# 47_VI-Camera_MIPI-CSI.net
KiCad netlist of a schematic drawn in Altium Designer
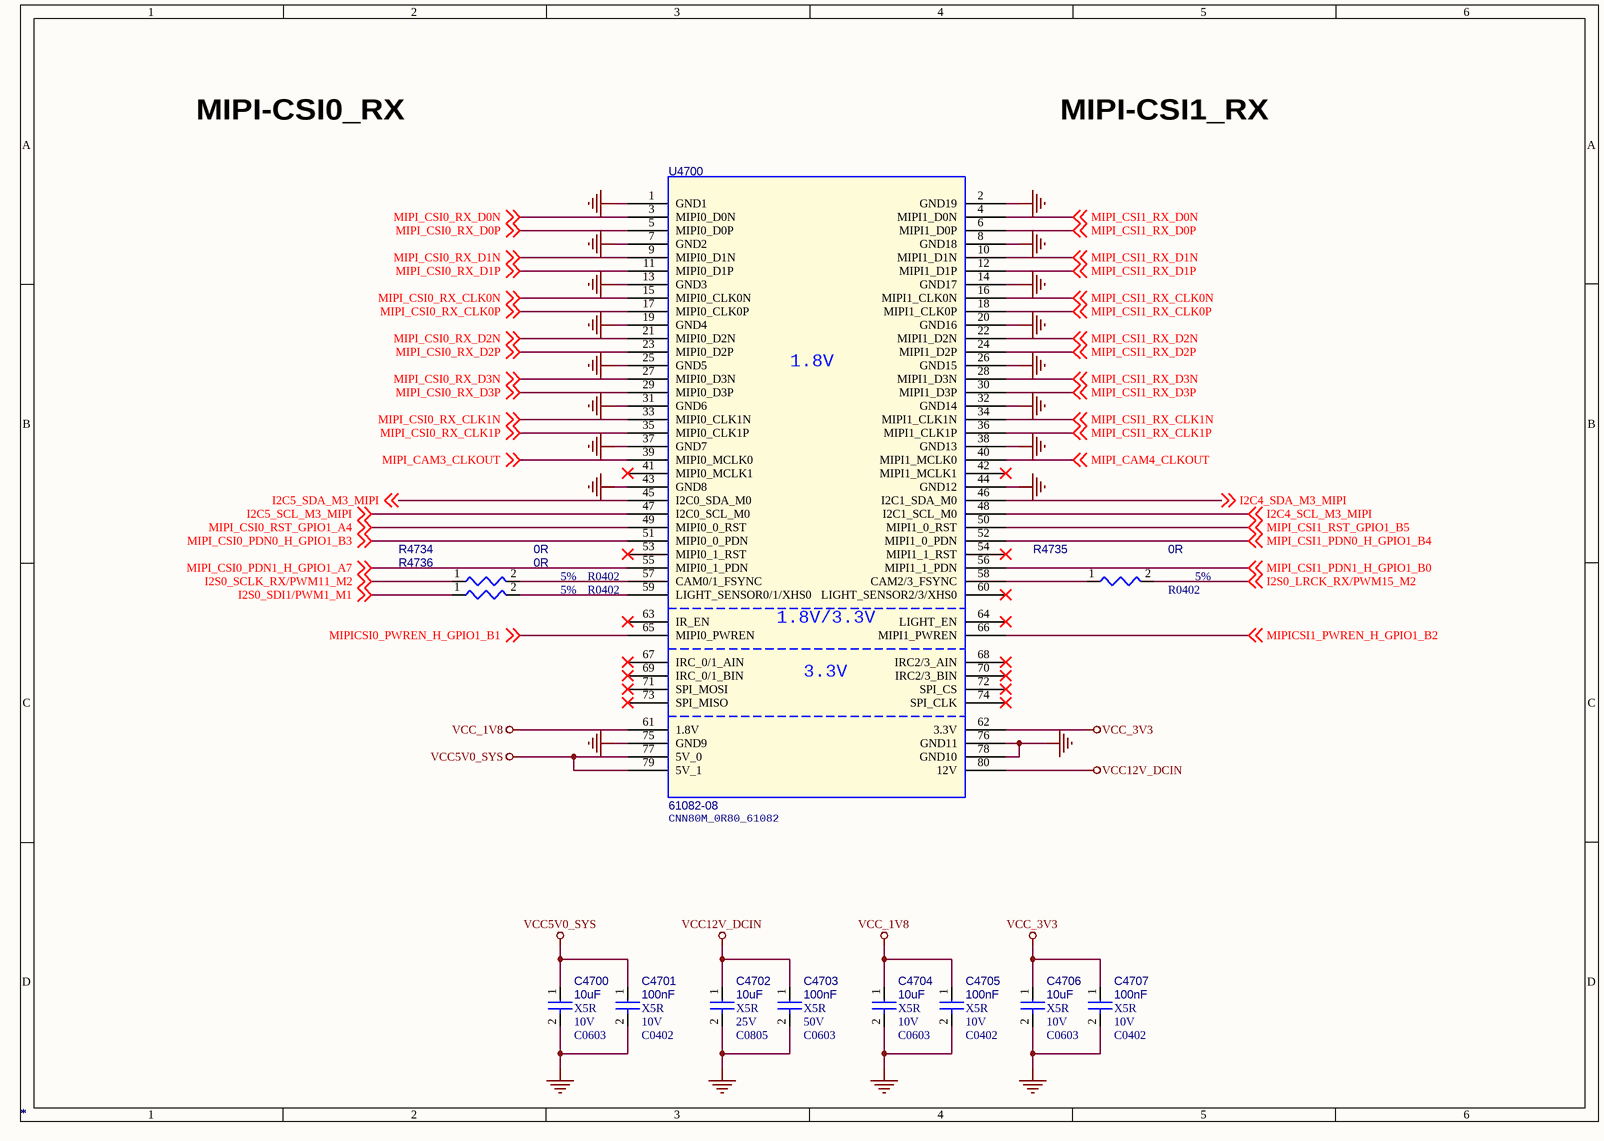
[diagram p0: 47.VI-Camera_MIPI-CSI.SchDoc]

(export (version "E")
  (design (tool "Eeschema 10.0.6"))
  (components
    (comp (ref "C4700")
      (value "*")
      (footprint "C0603")
      (description "cap,10.00uF,+/-10%,10V,X5R,C0603")
      (fields
        (field (name "VOLTAGE") "10V")
        (field (name "PCB FOOTPRINT") "C0603")
        (field (name "DIELECTRIC") "X5R")
        (field (name "TOLERANCE") "10%")
        (field (name "MANUFACTURER") "TDK")
        (field (name "ALTIUM_UNNAMED_1") "10uF")
        (field (name "CREATED BY") "JJJ")
      )
      (libsource (lib "*") (part "CAP NP"))
    )
    (comp (ref "C4701")
      (value "*")
      (footprint "C0402")
      (description "cap,100.00nF,+/-10%,10V,X5R,C0402")
      (fields
        (field (name "VOLTAGE") "10V")
        (field (name "PCB FOOTPRINT") "C0402")
        (field (name "DIELECTRIC") "X5R")
        (field (name "MANUFACTURER") "TDK")
        (field (name "TOLERANCE") "10%")
        (field (name "ALTIUM_UNNAMED_1") "100nF")
        (field (name "CREATED BY") "JJJ")
      )
      (libsource (lib "*") (part "CAP NP"))
    )
    (comp (ref "C4702")
      (value "*")
      (footprint "C0805")
      (description "cap,10.00uF,+/-10%,25V,X5R,C0805")
      (fields
        (field (name "VOLTAGE") "25V")
        (field (name "PCB FOOTPRINT") "C0805")
        (field (name "DIELECTRIC") "X5R")
        (field (name "TOLERANCE") "10%")
        (field (name "MANUFACTURER") "TDK")
        (field (name "ALTIUM_UNNAMED_1") "10uF")
        (field (name "CREATED BY") "JJJ")
      )
      (libsource (lib "*") (part "CAP NP"))
    )
    (comp (ref "C4703")
      (value "*")
      (footprint "C0603")
      (description "cap,100.00nF,+/-10%,50V,X5R,C0603")
      (fields
        (field (name "VOLTAGE") "50V")
        (field (name "PCB FOOTPRINT") "C0603")
        (field (name "DIELECTRIC") "X5R")
        (field (name "MANUFACTURER") "TDK")
        (field (name "TOLERANCE") "10%")
        (field (name "ALTIUM_UNNAMED_1") "100nF")
        (field (name "CREATED BY") "JJJ")
      )
      (libsource (lib "*") (part "CAP NP"))
    )
    (comp (ref "C4704")
      (value "*")
      (footprint "C0603")
      (description "cap,10.00uF,+/-10%,10V,X5R,C0603")
      (fields
        (field (name "VOLTAGE") "10V")
        (field (name "PCB FOOTPRINT") "C0603")
        (field (name "DIELECTRIC") "X5R")
        (field (name "TOLERANCE") "10%")
        (field (name "MANUFACTURER") "TDK")
        (field (name "ALTIUM_UNNAMED_1") "10uF")
        (field (name "CREATED BY") "JJJ")
      )
      (libsource (lib "*") (part "CAP NP"))
    )
    (comp (ref "C4705")
      (value "*")
      (footprint "C0402")
      (description "cap,100.00nF,+/-10%,10V,X5R,C0402")
      (fields
        (field (name "VOLTAGE") "10V")
        (field (name "PCB FOOTPRINT") "C0402")
        (field (name "DIELECTRIC") "X5R")
        (field (name "MANUFACTURER") "TDK")
        (field (name "TOLERANCE") "10%")
        (field (name "ALTIUM_UNNAMED_1") "100nF")
        (field (name "CREATED BY") "JJJ")
      )
      (libsource (lib "*") (part "CAP NP"))
    )
    (comp (ref "C4706")
      (value "*")
      (footprint "C0603")
      (description "cap,10.00uF,+/-10%,10V,X5R,C0603")
      (fields
        (field (name "VOLTAGE") "10V")
        (field (name "PCB FOOTPRINT") "C0603")
        (field (name "DIELECTRIC") "X5R")
        (field (name "TOLERANCE") "10%")
        (field (name "MANUFACTURER") "TDK")
        (field (name "ALTIUM_UNNAMED_1") "10uF")
        (field (name "CREATED BY") "JJJ")
      )
      (libsource (lib "*") (part "CAP NP"))
    )
    (comp (ref "C4707")
      (value "*")
      (footprint "C0402")
      (description "cap,100.00nF,+/-10%,10V,X5R,C0402")
      (fields
        (field (name "VOLTAGE") "10V")
        (field (name "PCB FOOTPRINT") "C0402")
        (field (name "DIELECTRIC") "X5R")
        (field (name "TOLERANCE") "10%")
        (field (name "MANUFACTURER") "TDK")
        (field (name "ALTIUM_UNNAMED_1") "100nF")
        (field (name "CREATED BY") "JJJ")
      )
      (libsource (lib "*") (part "CAP NP"))
    )
    (comp (ref "R4734")
      (value "*")
      (footprint "R0402")
      (description "НЁУГєсД¤µзЧи,0R,+/-5%,R0402,1/16W.")
      (fields
        (field (name "PCB FOOTPRINT") "R0402")
        (field (name "TOLERANCE") "5%")
        (field (name "MANUFACTURER") "YAGEO")
        (field (name "ALTIUM_UNNAMED_1") "0R")
        (field (name "CREATED BY") "YTL")
      )
      (libsource (lib "*") (part "RESISTOR_Dup1"))
    )
    (comp (ref "R4735")
      (value "*")
      (footprint "R0402")
      (description "НЁУГєсД¤µзЧи,0R,+/-5%,R0402,1/16W.")
      (fields
        (field (name "PCB FOOTPRINT") "R0402")
        (field (name "TOLERANCE") "5%")
        (field (name "MANUFACTURER") "YAGEO")
        (field (name "ALTIUM_UNNAMED_1") "0R")
        (field (name "CREATED BY") "YTL")
      )
      (libsource (lib "*") (part "RESISTOR_Dup1"))
    )
    (comp (ref "R4736")
      (value "*")
      (footprint "R0402")
      (description "НЁУГєсД¤µзЧи,0R,+/-5%,R0402,1/16W.")
      (fields
        (field (name "PCB FOOTPRINT") "R0402")
        (field (name "TOLERANCE") "5%")
        (field (name "MANUFACTURER") "YAGEO")
        (field (name "ALTIUM_UNNAMED_1") "0R")
        (field (name "CREATED BY") "YTL")
      )
      (libsource (lib "*") (part "RESISTOR_Dup1"))
    )
    (comp (ref "U4700")
      (value "*")
      (footprint "CNN80M_0R80_61082")
      (fields (field (name "PCB FOOTPRINT") "CNN80M_0R80_61082") (field (name "ALTIUM_UNNAMED_1") "61082-08"))
      (libsource (lib "*") (part "61082-08"))
    )
  )
  (nets
    (net (code "1") (name "GND") (class "Default")
      (node (ref "C4700") (pin "2") (pinfunction "2_2") (pintype "passive"))
      (node (ref "C4701") (pin "2") (pinfunction "2_2") (pintype "passive"))
      (node (ref "C4702") (pin "2") (pinfunction "2_2") (pintype "passive"))
      (node (ref "C4703") (pin "2") (pinfunction "2_2") (pintype "passive"))
      (node (ref "C4704") (pin "2") (pinfunction "2_2") (pintype "passive"))
      (node (ref "C4705") (pin "2") (pinfunction "2_2") (pintype "passive"))
      (node (ref "C4706") (pin "2") (pinfunction "2_2") (pintype "passive"))
      (node (ref "C4707") (pin "2") (pinfunction "2_2") (pintype "passive"))
      (node (ref "U4700") (pin "1") (pinfunction "GND1_1") (pintype "passive"))
      (node (ref "U4700") (pin "13") (pinfunction "GND3_13") (pintype "passive"))
      (node (ref "U4700") (pin "14") (pinfunction "GND17_14") (pintype "passive"))
      (node (ref "U4700") (pin "19") (pinfunction "GND4_19") (pintype "passive"))
      (node (ref "U4700") (pin "2") (pinfunction "GND19_2") (pintype "passive"))
      (node (ref "U4700") (pin "20") (pinfunction "GND16_20") (pintype "passive"))
      (node (ref "U4700") (pin "25") (pinfunction "GND5_25") (pintype "passive"))
      (node (ref "U4700") (pin "26") (pinfunction "GND15_26") (pintype "passive"))
      (node (ref "U4700") (pin "31") (pinfunction "GND6_31") (pintype "passive"))
      (node (ref "U4700") (pin "32") (pinfunction "GND14_32") (pintype "passive"))
      (node (ref "U4700") (pin "37") (pinfunction "GND7_37") (pintype "passive"))
      (node (ref "U4700") (pin "38") (pinfunction "GND13_38") (pintype "passive"))
      (node (ref "U4700") (pin "43") (pinfunction "GND8_43") (pintype "passive"))
      (node (ref "U4700") (pin "44") (pinfunction "GND12_44") (pintype "passive"))
      (node (ref "U4700") (pin "7") (pinfunction "GND2_7") (pintype "passive"))
      (node (ref "U4700") (pin "75") (pinfunction "GND9_75") (pintype "passive"))
      (node (ref "U4700") (pin "76") (pinfunction "GND11_76") (pintype "passive"))
      (node (ref "U4700") (pin "78") (pinfunction "GND10_78") (pintype "passive"))
      (node (ref "U4700") (pin "8") (pinfunction "GND18_8") (pintype "passive"))
    )
    (net (code "2") (name "I2C4_SCL_M3_MIPI") (class "Default")
      (node (ref "U4700") (pin "48") (pinfunction "I2C1_SCL_M0_48") (pintype "passive"))
    )
    (net (code "3") (name "I2C4_SDA_M3_MIPI") (class "Default")
      (node (ref "U4700") (pin "46") (pinfunction "I2C1_SDA_M0_46") (pintype "passive"))
    )
    (net (code "4") (name "I2C5_SCL_M3_MIPI") (class "Default")
      (node (ref "U4700") (pin "47") (pinfunction "I2C0_SCL_M0_47") (pintype "passive"))
    )
    (net (code "5") (name "I2C5_SDA_M3_MIPI") (class "Default")
      (node (ref "U4700") (pin "45") (pinfunction "I2C0_SDA_M0_45") (pintype "passive"))
    )
    (net (code "6") (name "I2S0_LRCK_RX{slash}PWM15_M2") (class "Default")
      (node (ref "R4735") (pin "2") (pinfunction "2_2") (pintype "passive"))
    )
    (net (code "7") (name "I2S0_SCLK_RX{slash}PWM11_M2") (class "Default")
      (node (ref "R4734") (pin "1") (pinfunction "1_1") (pintype "passive"))
    )
    (net (code "8") (name "I2S0_SDI1{slash}PWM1_M1") (class "Default")
      (node (ref "R4736") (pin "1") (pinfunction "1_1") (pintype "passive"))
    )
    (net (code "9") (name "MIPICSI0_PWREN_H_GPIO1_B1") (class "Default")
      (node (ref "U4700") (pin "65") (pinfunction "MIPI0_PWREN_65") (pintype "passive"))
    )
    (net (code "10") (name "MIPICSI1_PWREN_H_GPIO1_B2") (class "Default")
      (node (ref "U4700") (pin "66") (pinfunction "MIPI1_PWREN_66") (pintype "passive"))
    )
    (net (code "11") (name "MIPI_CAM3_CLKOUT") (class "Default")
      (node (ref "U4700") (pin "39") (pinfunction "MIPI0_MCLK0_39") (pintype "passive"))
    )
    (net (code "12") (name "MIPI_CAM4_CLKOUT") (class "Default")
      (node (ref "U4700") (pin "40") (pinfunction "MIPI1_MCLK0_40") (pintype "passive"))
    )
    (net (code "13") (name "MIPI_CSI0_PDN0_H_GPIO1_B3") (class "Default")
      (node (ref "U4700") (pin "51") (pinfunction "MIPI0_0_PDN_51") (pintype "passive"))
    )
    (net (code "14") (name "MIPI_CSI0_PDN1_H_GPIO1_A7") (class "Default")
      (node (ref "U4700") (pin "55") (pinfunction "MIPI0_1_PDN_55") (pintype "passive"))
    )
    (net (code "15") (name "MIPI_CSI0_RST_GPIO1_A4") (class "Default")
      (node (ref "U4700") (pin "49") (pinfunction "MIPI0_0_RST_49") (pintype "passive"))
    )
    (net (code "16") (name "MIPI_CSI0_RX_CLK0N") (class "Default")
      (node (ref "U4700") (pin "15") (pinfunction "MIPI0_CLK0N_15") (pintype "passive"))
    )
    (net (code "17") (name "MIPI_CSI0_RX_CLK0P") (class "Default")
      (node (ref "U4700") (pin "17") (pinfunction "MIPI0_CLK0P_17") (pintype "passive"))
    )
    (net (code "18") (name "MIPI_CSI0_RX_CLK1N") (class "Default")
      (node (ref "U4700") (pin "33") (pinfunction "MIPI0_CLK1N_33") (pintype "passive"))
    )
    (net (code "19") (name "MIPI_CSI0_RX_CLK1P") (class "Default")
      (node (ref "U4700") (pin "35") (pinfunction "MIPI0_CLK1P_35") (pintype "passive"))
    )
    (net (code "20") (name "MIPI_CSI0_RX_D0N") (class "Default")
      (node (ref "U4700") (pin "3") (pinfunction "MIPI0_D0N_3") (pintype "passive"))
    )
    (net (code "21") (name "MIPI_CSI0_RX_D0P") (class "Default")
      (node (ref "U4700") (pin "5") (pinfunction "MIPI0_D0P_5") (pintype "passive"))
    )
    (net (code "22") (name "MIPI_CSI0_RX_D1N") (class "Default")
      (node (ref "U4700") (pin "9") (pinfunction "MIPI0_D1N_9") (pintype "passive"))
    )
    (net (code "23") (name "MIPI_CSI0_RX_D1P") (class "Default")
      (node (ref "U4700") (pin "11") (pinfunction "MIPI0_D1P_11") (pintype "passive"))
    )
    (net (code "24") (name "MIPI_CSI0_RX_D2N") (class "Default")
      (node (ref "U4700") (pin "21") (pinfunction "MIPI0_D2N_21") (pintype "passive"))
    )
    (net (code "25") (name "MIPI_CSI0_RX_D2P") (class "Default")
      (node (ref "U4700") (pin "23") (pinfunction "MIPI0_D2P_23") (pintype "passive"))
    )
    (net (code "26") (name "MIPI_CSI0_RX_D3N") (class "Default")
      (node (ref "U4700") (pin "27") (pinfunction "MIPI0_D3N_27") (pintype "passive"))
    )
    (net (code "27") (name "MIPI_CSI0_RX_D3P") (class "Default")
      (node (ref "U4700") (pin "29") (pinfunction "MIPI0_D3P_29") (pintype "passive"))
    )
    (net (code "28") (name "MIPI_CSI1_PDN0_H_GPIO1_B4") (class "Default")
      (node (ref "U4700") (pin "52") (pinfunction "MIPI1_0_PDN_52") (pintype "passive"))
    )
    (net (code "29") (name "MIPI_CSI1_PDN1_H_GPIO1_B0") (class "Default")
      (node (ref "U4700") (pin "56") (pinfunction "MIPI1_1_PDN_56") (pintype "passive"))
    )
    (net (code "30") (name "MIPI_CSI1_RST_GPIO1_B5") (class "Default")
      (node (ref "U4700") (pin "50") (pinfunction "MIPI1_0_RST_50") (pintype "passive"))
    )
    (net (code "31") (name "MIPI_CSI1_RX_CLK0N") (class "Default")
      (node (ref "U4700") (pin "16") (pinfunction "MIPI1_CLK0N_16") (pintype "passive"))
    )
    (net (code "32") (name "MIPI_CSI1_RX_CLK0P") (class "Default")
      (node (ref "U4700") (pin "18") (pinfunction "MIPI1_CLK0P_18") (pintype "passive"))
    )
    (net (code "33") (name "MIPI_CSI1_RX_CLK1N") (class "Default")
      (node (ref "U4700") (pin "34") (pinfunction "MIPI1_CLK1N_34") (pintype "passive"))
    )
    (net (code "34") (name "MIPI_CSI1_RX_CLK1P") (class "Default")
      (node (ref "U4700") (pin "36") (pinfunction "MIPI1_CLK1P_36") (pintype "passive"))
    )
    (net (code "35") (name "MIPI_CSI1_RX_D0N") (class "Default")
      (node (ref "U4700") (pin "4") (pinfunction "MIPI1_D0N_4") (pintype "passive"))
    )
    (net (code "36") (name "MIPI_CSI1_RX_D0P") (class "Default")
      (node (ref "U4700") (pin "6") (pinfunction "MIPI1_D0P_6") (pintype "passive"))
    )
    (net (code "37") (name "MIPI_CSI1_RX_D1N") (class "Default")
      (node (ref "U4700") (pin "10") (pinfunction "MIPI1_D1N_10") (pintype "passive"))
    )
    (net (code "38") (name "MIPI_CSI1_RX_D1P") (class "Default")
      (node (ref "U4700") (pin "12") (pinfunction "MIPI1_D1P_12") (pintype "passive"))
    )
    (net (code "39") (name "MIPI_CSI1_RX_D2N") (class "Default")
      (node (ref "U4700") (pin "22") (pinfunction "MIPI1_D2N_22") (pintype "passive"))
    )
    (net (code "40") (name "MIPI_CSI1_RX_D2P") (class "Default")
      (node (ref "U4700") (pin "24") (pinfunction "MIPI1_D2P_24") (pintype "passive"))
    )
    (net (code "41") (name "MIPI_CSI1_RX_D3N") (class "Default")
      (node (ref "U4700") (pin "28") (pinfunction "MIPI1_D3N_28") (pintype "passive"))
    )
    (net (code "42") (name "MIPI_CSI1_RX_D3P") (class "Default")
      (node (ref "U4700") (pin "30") (pinfunction "MIPI1_D3P_30") (pintype "passive"))
    )
    (net (code "43") (name "Net-(U4700-CAM0{slash}1_FSYNC)") (class "Default")
      (node (ref "R4734") (pin "2") (pinfunction "2_2") (pintype "passive"))
      (node (ref "U4700") (pin "57") (pinfunction "CAM0/1_FSYNC_57") (pintype "passive"))
    )
    (net (code "44") (name "Net-(U4700-CAM2{slash}3_FSYNC)") (class "Default")
      (node (ref "R4735") (pin "1") (pinfunction "1_1") (pintype "passive"))
      (node (ref "U4700") (pin "58") (pinfunction "CAM2/3_FSYNC_58") (pintype "passive"))
    )
    (net (code "45") (name "Net-(U4700-LIGHT_SENSOR0{slash}1{slash}XHS0)") (class "Default")
      (node (ref "R4736") (pin "2") (pinfunction "2_2") (pintype "passive"))
      (node (ref "U4700") (pin "59") (pinfunction "LIGHT_SENSOR0/1/XHS0_59") (pintype "passive"))
    )
    (net (code "46") (name "VCC5V0_SYS") (class "Default")
      (node (ref "C4700") (pin "1") (pinfunction "1_1") (pintype "passive"))
      (node (ref "C4701") (pin "1") (pinfunction "1_1") (pintype "passive"))
      (node (ref "U4700") (pin "77") (pinfunction "5V_0_77") (pintype "passive"))
      (node (ref "U4700") (pin "79") (pinfunction "5V_1_79") (pintype "passive"))
    )
    (net (code "47") (name "VCC12V_DCIN") (class "Default")
      (node (ref "C4702") (pin "1") (pinfunction "1_1") (pintype "passive"))
      (node (ref "C4703") (pin "1") (pinfunction "1_1") (pintype "passive"))
      (node (ref "U4700") (pin "80") (pinfunction "12V_80") (pintype "passive"))
    )
    (net (code "48") (name "VCC_1V8") (class "Default")
      (node (ref "C4704") (pin "1") (pinfunction "1_1") (pintype "passive"))
      (node (ref "C4705") (pin "1") (pinfunction "1_1") (pintype "passive"))
      (node (ref "U4700") (pin "61") (pinfunction "1.8V_61") (pintype "passive"))
    )
    (net (code "49") (name "VCC_3V3") (class "Default")
      (node (ref "C4706") (pin "1") (pinfunction "1_1") (pintype "passive"))
      (node (ref "C4707") (pin "1") (pinfunction "1_1") (pintype "passive"))
      (node (ref "U4700") (pin "62") (pinfunction "3.3V_62") (pintype "passive"))
    )
    (net (code "50") (name "unconnected-(U4700-IRC2{slash}3_AIN-Pad68)") (class "Default")
      (node (ref "U4700") (pin "68") (pinfunction "IRC2/3_AIN_68") (pintype "passive+no_connect"))
    )
    (net (code "51") (name "unconnected-(U4700-IRC2{slash}3_BIN-Pad70)") (class "Default")
      (node (ref "U4700") (pin "70") (pinfunction "IRC2/3_BIN_70") (pintype "passive+no_connect"))
    )
    (net (code "52") (name "unconnected-(U4700-IRC_0{slash}1_AIN-Pad67)") (class "Default")
      (node (ref "U4700") (pin "67") (pinfunction "IRC_0/1_AIN_67") (pintype "passive+no_connect"))
    )
    (net (code "53") (name "unconnected-(U4700-IRC_0{slash}1_BIN-Pad69)") (class "Default")
      (node (ref "U4700") (pin "69") (pinfunction "IRC_0/1_BIN_69") (pintype "passive+no_connect"))
    )
    (net (code "54") (name "unconnected-(U4700-IR_EN-Pad63)") (class "Default")
      (node (ref "U4700") (pin "63") (pinfunction "IR_EN_63") (pintype "passive+no_connect"))
    )
    (net (code "55") (name "unconnected-(U4700-LIGHT_EN-Pad64)") (class "Default")
      (node (ref "U4700") (pin "64") (pinfunction "LIGHT_EN_64") (pintype "passive+no_connect"))
    )
    (net (code "56") (name "unconnected-(U4700-LIGHT_SENSOR2{slash}3{slash}XHS0-Pad60)") (class "Default")
      (node (ref "U4700") (pin "60") (pinfunction "LIGHT_SENSOR2/3/XHS0_60") (pintype "passive+no_connect"))
    )
    (net (code "57") (name "unconnected-(U4700-MIPI0_1_RST-Pad53)") (class "Default")
      (node (ref "U4700") (pin "53") (pinfunction "MIPI0_1_RST_53") (pintype "passive+no_connect"))
    )
    (net (code "58") (name "unconnected-(U4700-MIPI0_MCLK1-Pad41)") (class "Default")
      (node (ref "U4700") (pin "41") (pinfunction "MIPI0_MCLK1_41") (pintype "passive+no_connect"))
    )
    (net (code "59") (name "unconnected-(U4700-MIPI1_1_RST-Pad54)") (class "Default")
      (node (ref "U4700") (pin "54") (pinfunction "MIPI1_1_RST_54") (pintype "passive+no_connect"))
    )
    (net (code "60") (name "unconnected-(U4700-MIPI1_MCLK1-Pad42)") (class "Default")
      (node (ref "U4700") (pin "42") (pinfunction "MIPI1_MCLK1_42") (pintype "passive+no_connect"))
    )
    (net (code "61") (name "unconnected-(U4700-SPI_CLK-Pad74)") (class "Default")
      (node (ref "U4700") (pin "74") (pinfunction "SPI_CLK_74") (pintype "passive+no_connect"))
    )
    (net (code "62") (name "unconnected-(U4700-SPI_CS-Pad72)") (class "Default")
      (node (ref "U4700") (pin "72") (pinfunction "SPI_CS_72") (pintype "passive+no_connect"))
    )
    (net (code "63") (name "unconnected-(U4700-SPI_MISO-Pad73)") (class "Default")
      (node (ref "U4700") (pin "73") (pinfunction "SPI_MISO_73") (pintype "passive+no_connect"))
    )
    (net (code "64") (name "unconnected-(U4700-SPI_MOSI-Pad71)") (class "Default")
      (node (ref "U4700") (pin "71") (pinfunction "SPI_MOSI_71") (pintype "passive+no_connect"))
    )
  )
)
